# module.net
KiCad netlist of a schematic drawn in EAGLE
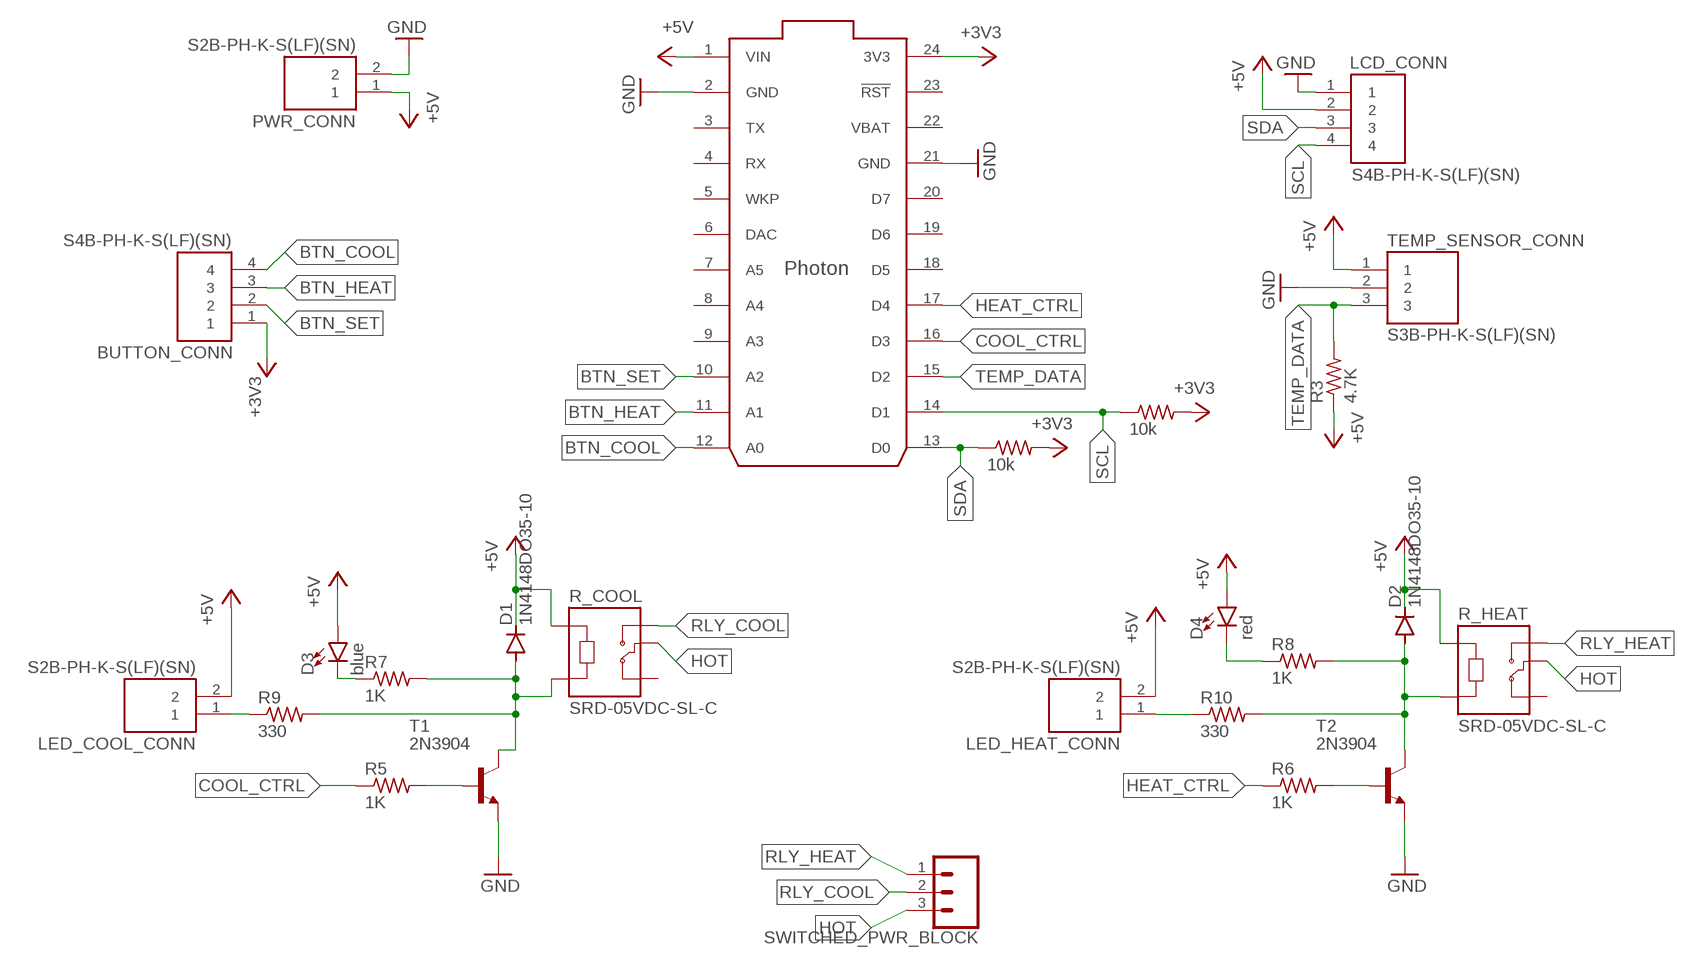
[diagram p0: schematic, sheet 1]

(export (version "E")
  (design (tool "Eeschema 10.0.6"))
  (components
    (comp (ref "BUTTON_CONN")
      (value "S4B-PH-K-S(LF)(SN)")
      (footprint "eagle-import:JST_S4B-PH-K-S(LF)(SN)")
      (fields
        (field (name "MF") "JST Sales")
        (field (name "MF_1") "JST (JAPAN SOLDERLESS TERMINALS)")
        (field (name "MPN") "S4B-PH-K-S (LF)(SN)")
      )
      (libsource (lib "eagle-import") (part "S4B-PH-K-S(LF)(SN)"))
    )
    (comp (ref "D1")
      (value "1N4148DO35-10")
      (footprint "eagle-import:DO35-10")
      (fields (field (name "MF") "MULTICOMP PRO") (field (name "MPN") "1N4148 (DO-35)"))
      (libsource (lib "eagle-import") (part "1N4148DO35-10"))
    )
    (comp (ref "D2")
      (value "1N4148DO35-10")
      (footprint "eagle-import:DO35-10")
      (fields (field (name "MF") "MULTICOMP PRO") (field (name "MPN") "1N4148 (DO-35)"))
      (libsource (lib "eagle-import") (part "1N4148DO35-10"))
    )
    (comp (ref "D3")
      (value "blue")
      (footprint "eagle-import:LED_3MM")
      (fields (field (name "MF") "VISHAY") (field (name "MPN") "TLHB4400"))
      (libsource (lib "eagle-import") (part "LED3MM"))
    )
    (comp (ref "D4")
      (value "red")
      (footprint "eagle-import:LED_3MM")
      (fields (field (name "MF") "VCC (VISUAL COMMUNICATIONS COMPANY)") (field (name "MPN") "4300F1LC"))
      (libsource (lib "eagle-import") (part "LED3MM"))
    )
    (comp (ref "LCD_CONN")
      (value "S4B-PH-K-S(LF)(SN)")
      (footprint "eagle-import:JST_S4B-PH-K-S(LF)(SN)")
      (fields
        (field (name "MF") "JST Sales")
        (field (name "MF_1") "JST (JAPAN SOLDERLESS TERMINALS)")
        (field (name "MPN") "S4B-PH-K-S (LF)(SN)")
      )
      (libsource (lib "eagle-import") (part "S4B-PH-K-S(LF)(SN)"))
    )
    (comp (ref "LED_COOL_CONN")
      (value "S2B-PH-K-S(LF)(SN)")
      (footprint "eagle-import:JST_S2B-PH-K-S(LF)(SN)")
      (fields
        (field (name "MF") "JST Sales America Inc.")
        (field (name "MF_1") "JST (JAPAN SOLDERLESS TERMINALS)")
        (field (name "MPN") "S2B-PH-K-S (LF)(SN)")
      )
      (libsource (lib "eagle-import") (part "S2B-PH-K-S(LF)(SN)"))
    )
    (comp (ref "LED_HEAT_CONN")
      (value "S2B-PH-K-S(LF)(SN)")
      (footprint "eagle-import:JST_S2B-PH-K-S(LF)(SN)")
      (fields
        (field (name "MF") "JST Sales America Inc.")
        (field (name "MF_1") "JST (JAPAN SOLDERLESS TERMINALS)")
        (field (name "MPN") "S2B-PH-K-S (LF)(SN)")
      )
      (libsource (lib "eagle-import") (part "S2B-PH-K-S(LF)(SN)"))
    )
    (comp (ref "PWR_CONN")
      (value "S2B-PH-K-S(LF)(SN)")
      (footprint "eagle-import:JST_S2B-PH-K-S(LF)(SN)")
      (fields
        (field (name "MF") "JST Sales America Inc.")
        (field (name "MF_1") "JST (JAPAN SOLDERLESS TERMINALS)")
        (field (name "MPN") "S2B-PH-K-S (LF)(SN)")
      )
      (libsource (lib "eagle-import") (part "S2B-PH-K-S(LF)(SN)"))
    )
    (comp (ref "R1")
      (value "10k")
      (footprint "eagle-import:0207_10")
      (libsource (lib "eagle-import") (part "R-US_0207/10"))
    )
    (comp (ref "R2")
      (value "10k")
      (footprint "eagle-import:0207_10")
      (libsource (lib "eagle-import") (part "R-US_0207/10"))
    )
    (comp (ref "R3")
      (value "4.7K")
      (footprint "eagle-import:0207_10")
      (libsource (lib "eagle-import") (part "R-US_0207/10"))
    )
    (comp (ref "R5")
      (value "1K")
      (footprint "eagle-import:0207_10")
      (libsource (lib "eagle-import") (part "R-US_0207/10"))
    )
    (comp (ref "R6")
      (value "1K")
      (footprint "eagle-import:0207_10")
      (libsource (lib "eagle-import") (part "R-US_0207/10"))
    )
    (comp (ref "R7")
      (value "1K")
      (footprint "eagle-import:0207_10")
      (libsource (lib "eagle-import") (part "R-US_0207/10"))
    )
    (comp (ref "R8")
      (value "1K")
      (footprint "eagle-import:0207_10")
      (libsource (lib "eagle-import") (part "R-US_0207/10"))
    )
    (comp (ref "R9")
      (value "330")
      (footprint "eagle-import:0207_10")
      (libsource (lib "eagle-import") (part "R-US_0207/10"))
    )
    (comp (ref "R10")
      (value "330")
      (footprint "eagle-import:0207_10")
      (libsource (lib "eagle-import") (part "R-US_0207/10"))
    )
    (comp (ref "R_COOL")
      (value "SRD-05VDC-SL-C")
      (footprint "eagle-import:RELAY_SRD-05VDC-SL-C")
      (fields (field (name "MF") "Songle Relay"))
      (libsource (lib "eagle-import") (part "SRD-05VDC-SL-C"))
    )
    (comp (ref "R_HEAT")
      (value "SRD-05VDC-SL-C")
      (footprint "eagle-import:RELAY_SRD-05VDC-SL-C")
      (fields (field (name "MF") "Songle Relay"))
      (libsource (lib "eagle-import") (part "SRD-05VDC-SL-C"))
    )
    (comp (ref "SWITCHED_PWR_BLOCK")
      (value "CONN_03-SCREW-5MM")
      (footprint "eagle-import:SCREWTERMINAL-5MM-3")
      (libsource (lib "eagle-import") (part "CONN_03-SCREW-5MM"))
    )
    (comp (ref "T1")
      (value "2N3904")
      (footprint "eagle-import:TO92")
      (fields (field (name "MF") "ONSEMI") (field (name "MPN") "2N3904TF"))
      (libsource (lib "eagle-import") (part "2N3904"))
    )
    (comp (ref "T2")
      (value "2N3904")
      (footprint "eagle-import:TO92")
      (fields (field (name "MF") "ONSEMI") (field (name "MPN") "2N3904TF"))
      (libsource (lib "eagle-import") (part "2N3904"))
    )
    (comp (ref "TEMP_SENSOR_CONN")
      (value "S3B-PH-K-S(LF)(SN)")
      (footprint "eagle-import:JST_S3B-PH-K-S(LF)(SN)")
      (fields
        (field (name "DIGI-KEY_PART_NUMBER") "455-1720-ND")
        (field (name "MF") "JST Sales")
        (field (name "MF_1") "JST (JAPAN SOLDERLESS TERMINALS)")
        (field (name "MPN") "S3B-PH-K-S (LF)(SN)")
      )
      (libsource (lib "eagle-import") (part "S3B-PH-K-S(LF)(SN)"))
    )
    (comp (ref "U$1")
      (value "PHOTON_WITH_HEADERS")
      (footprint "eagle-import:PHOTON")
      (fields (field (name "MF") "PARTICLE") (field (name "MPN") "PHOTONH"))
      (libsource (lib "eagle-import") (part "PHOTON_WITH_HEADERS"))
    )
  )
  (nets
    (net (code "1") (name "+3V3") (class "Default")
      (node (ref "BUTTON_CONN") (pin "1") (pinfunction "1_1") (pintype "passive"))
      (node (ref "R1") (pin "2") (pinfunction "2_2") (pintype "passive"))
      (node (ref "R2") (pin "2") (pinfunction "2_2") (pintype "passive"))
      (node (ref "U$1") (pin "24") (pinfunction "3V3_24") (pintype "power_in"))
    )
    (net (code "2") (name "+5V") (class "Default")
      (node (ref "D1") (pin "C") (pinfunction "C_C") (pintype "passive"))
      (node (ref "D2") (pin "C") (pinfunction "C_C") (pintype "passive"))
      (node (ref "D3") (pin "A") (pinfunction "A_A") (pintype "passive"))
      (node (ref "D4") (pin "A") (pinfunction "A_A") (pintype "passive"))
      (node (ref "LCD_CONN") (pin "2") (pinfunction "2_2") (pintype "passive"))
      (node (ref "LED_COOL_CONN") (pin "2") (pinfunction "2_2") (pintype "passive"))
      (node (ref "LED_HEAT_CONN") (pin "2") (pinfunction "2_2") (pintype "passive"))
      (node (ref "PWR_CONN") (pin "1") (pinfunction "1_1") (pintype "passive"))
      (node (ref "R3") (pin "1") (pinfunction "1_1") (pintype "passive"))
      (node (ref "R_COOL") (pin "A1") (pinfunction "A1_A1") (pintype "passive"))
      (node (ref "R_HEAT") (pin "A1") (pinfunction "A1_A1") (pintype "passive"))
      (node (ref "TEMP_SENSOR_CONN") (pin "1") (pinfunction "1_1") (pintype "passive"))
      (node (ref "U$1") (pin "1") (pinfunction "VIN_1") (pintype "power_in"))
    )
    (net (code "3") (name "/VBAT") (class "Default")
      (node (ref "U$1") (pin "22") (pinfunction "VBAT_22") (pintype "power_in"))
    )
    (net (code "4") (name "BTN_COOL") (class "Default")
      (node (ref "BUTTON_CONN") (pin "4") (pinfunction "4_4") (pintype "passive"))
      (node (ref "U$1") (pin "12") (pinfunction "A0_12") (pintype "bidirectional"))
    )
    (net (code "5") (name "BTN_HEAT") (class "Default")
      (node (ref "BUTTON_CONN") (pin "3") (pinfunction "3_3") (pintype "passive"))
      (node (ref "U$1") (pin "11") (pinfunction "A1_11") (pintype "bidirectional"))
    )
    (net (code "6") (name "BTN_SET") (class "Default")
      (node (ref "BUTTON_CONN") (pin "2") (pinfunction "2_2") (pintype "passive"))
      (node (ref "U$1") (pin "10") (pinfunction "A2_10") (pintype "bidirectional"))
    )
    (net (code "7") (name "COOL_CTRL") (class "Default")
      (node (ref "R5") (pin "1") (pinfunction "1_1") (pintype "passive"))
      (node (ref "U$1") (pin "16") (pinfunction "D3_16") (pintype "bidirectional"))
    )
    (net (code "8") (name "GND") (class "Default")
      (node (ref "LCD_CONN") (pin "1") (pinfunction "1_1") (pintype "passive"))
      (node (ref "PWR_CONN") (pin "2") (pinfunction "2_2") (pintype "passive"))
      (node (ref "T1") (pin "3") (pinfunction "E_3") (pintype "passive"))
      (node (ref "T2") (pin "3") (pinfunction "E_3") (pintype "passive"))
      (node (ref "TEMP_SENSOR_CONN") (pin "2") (pinfunction "2_2") (pintype "passive"))
      (node (ref "U$1") (pin "2") (pinfunction "GND_2") (pintype "power_in"))
      (node (ref "U$1") (pin "21") (pinfunction "GND_21") (pintype "power_in"))
    )
    (net (code "9") (name "HEAT_CTRL") (class "Default")
      (node (ref "R6") (pin "1") (pinfunction "1_1") (pintype "passive"))
      (node (ref "U$1") (pin "17") (pinfunction "D4_17") (pintype "bidirectional"))
    )
    (net (code "10") (name "HOT") (class "Default")
      (node (ref "R_COOL") (pin "COM") (pinfunction "COM_COM") (pintype "passive"))
      (node (ref "R_HEAT") (pin "COM") (pinfunction "COM_COM") (pintype "passive"))
      (node (ref "SWITCHED_PWR_BLOCK") (pin "3") (pinfunction "3_3") (pintype "passive"))
    )
    (net (code "11") (name "Net-(D3-C)") (class "Default")
      (node (ref "D3") (pin "K") (pinfunction "C_K") (pintype "passive"))
      (node (ref "R7") (pin "1") (pinfunction "1_1") (pintype "passive"))
    )
    (net (code "12") (name "Net-(D4-C)") (class "Default")
      (node (ref "D4") (pin "K") (pinfunction "C_K") (pintype "passive"))
      (node (ref "R8") (pin "1") (pinfunction "1_1") (pintype "passive"))
    )
    (net (code "13") (name "Net-(LED_COOL_CONN-Pad1)") (class "Default")
      (node (ref "LED_COOL_CONN") (pin "1") (pinfunction "1_1") (pintype "passive"))
      (node (ref "R9") (pin "1") (pinfunction "1_1") (pintype "passive"))
    )
    (net (code "14") (name "Net-(LED_HEAT_CONN-Pad1)") (class "Default")
      (node (ref "LED_HEAT_CONN") (pin "1") (pinfunction "1_1") (pintype "passive"))
      (node (ref "R10") (pin "1") (pinfunction "1_1") (pintype "passive"))
    )
    (net (code "15") (name "Net-(T1-B)") (class "Default")
      (node (ref "R5") (pin "2") (pinfunction "2_2") (pintype "passive"))
      (node (ref "T1") (pin "2") (pinfunction "B_2") (pintype "passive"))
    )
    (net (code "16") (name "Net-(T1-C)") (class "Default")
      (node (ref "D1") (pin "A") (pinfunction "A_A") (pintype "passive"))
      (node (ref "R7") (pin "2") (pinfunction "2_2") (pintype "passive"))
      (node (ref "R9") (pin "2") (pinfunction "2_2") (pintype "passive"))
      (node (ref "R_COOL") (pin "A2") (pinfunction "A2_A2") (pintype "passive"))
      (node (ref "T1") (pin "1") (pinfunction "C_1") (pintype "passive"))
    )
    (net (code "17") (name "Net-(T2-B)") (class "Default")
      (node (ref "R6") (pin "2") (pinfunction "2_2") (pintype "passive"))
      (node (ref "T2") (pin "2") (pinfunction "B_2") (pintype "passive"))
    )
    (net (code "18") (name "Net-(T2-C)") (class "Default")
      (node (ref "D2") (pin "A") (pinfunction "A_A") (pintype "passive"))
      (node (ref "R10") (pin "2") (pinfunction "2_2") (pintype "passive"))
      (node (ref "R8") (pin "2") (pinfunction "2_2") (pintype "passive"))
      (node (ref "R_HEAT") (pin "A2") (pinfunction "A2_A2") (pintype "passive"))
      (node (ref "T2") (pin "1") (pinfunction "C_1") (pintype "passive"))
    )
    (net (code "19") (name "RLY_COOL") (class "Default")
      (node (ref "R_COOL") (pin "NO") (pinfunction "NO_NO") (pintype "passive"))
      (node (ref "SWITCHED_PWR_BLOCK") (pin "2") (pinfunction "2_2") (pintype "passive"))
    )
    (net (code "20") (name "RLY_HEAT") (class "Default")
      (node (ref "R_HEAT") (pin "NO") (pinfunction "NO_NO") (pintype "passive"))
      (node (ref "SWITCHED_PWR_BLOCK") (pin "1") (pinfunction "1_1") (pintype "passive"))
    )
    (net (code "21") (name "SCL") (class "Default")
      (node (ref "LCD_CONN") (pin "4") (pinfunction "4_4") (pintype "passive"))
      (node (ref "R1") (pin "1") (pinfunction "1_1") (pintype "passive"))
      (node (ref "U$1") (pin "14") (pinfunction "D1_14") (pintype "bidirectional"))
    )
    (net (code "22") (name "SDA") (class "Default")
      (node (ref "LCD_CONN") (pin "3") (pinfunction "3_3") (pintype "passive"))
      (node (ref "R2") (pin "1") (pinfunction "1_1") (pintype "passive"))
      (node (ref "U$1") (pin "13") (pinfunction "D0_13") (pintype "bidirectional"))
    )
    (net (code "23") (name "TEMP_DATA") (class "Default")
      (node (ref "R3") (pin "2") (pinfunction "2_2") (pintype "passive"))
      (node (ref "TEMP_SENSOR_CONN") (pin "3") (pinfunction "3_3") (pintype "passive"))
      (node (ref "U$1") (pin "15") (pinfunction "D2_15") (pintype "bidirectional"))
    )
    (net (code "24") (name "unconnected-(R_COOL-PadNC)") (class "Default")
      (node (ref "R_COOL") (pin "NC") (pinfunction "NC_NC") (pintype "passive"))
    )
    (net (code "25") (name "unconnected-(R_HEAT-PadNC)") (class "Default")
      (node (ref "R_HEAT") (pin "NC") (pinfunction "NC_NC") (pintype "passive"))
    )
    (net (code "26") (name "unconnected-(U$1-A3-Pad9)") (class "Default")
      (node (ref "U$1") (pin "9") (pinfunction "A3_9") (pintype "bidirectional"))
    )
    (net (code "27") (name "unconnected-(U$1-A4-Pad8)") (class "Default")
      (node (ref "U$1") (pin "8") (pinfunction "A4_8") (pintype "bidirectional"))
    )
    (net (code "28") (name "unconnected-(U$1-A5-Pad7)") (class "Default")
      (node (ref "U$1") (pin "7") (pinfunction "A5_7") (pintype "bidirectional"))
    )
    (net (code "29") (name "unconnected-(U$1-D5-Pad18)") (class "Default")
      (node (ref "U$1") (pin "18") (pinfunction "D5_18") (pintype "bidirectional"))
    )
    (net (code "30") (name "unconnected-(U$1-D6-Pad19)") (class "Default")
      (node (ref "U$1") (pin "19") (pinfunction "D6_19") (pintype "bidirectional"))
    )
    (net (code "31") (name "unconnected-(U$1-D7-Pad20)") (class "Default")
      (node (ref "U$1") (pin "20") (pinfunction "D7_20") (pintype "bidirectional"))
    )
    (net (code "32") (name "unconnected-(U$1-DAC-Pad6)") (class "Default")
      (node (ref "U$1") (pin "6") (pinfunction "DAC_6") (pintype "bidirectional"))
    )
    (net (code "33") (name "unconnected-(U$1-RX-Pad4)") (class "Default")
      (node (ref "U$1") (pin "4") (pinfunction "RX_4") (pintype "bidirectional"))
    )
    (net (code "34") (name "unconnected-(U$1-TX-Pad3)") (class "Default")
      (node (ref "U$1") (pin "3") (pinfunction "TX_3") (pintype "bidirectional"))
    )
    (net (code "35") (name "unconnected-(U$1-WKP-Pad5)") (class "Default")
      (node (ref "U$1") (pin "5") (pinfunction "WKP_5") (pintype "bidirectional"))
    )
    (net (code "36") (name "unconnected-(U$1-~{RST}-Pad23)") (class "Default")
      (node (ref "U$1") (pin "23") (pinfunction "~{RST}_23") (pintype "bidirectional"))
    )
  )
)
